# SHDN-IMD-S06-V00-PSU.net
KiCad netlist of a schematic drawn in Altium Designer
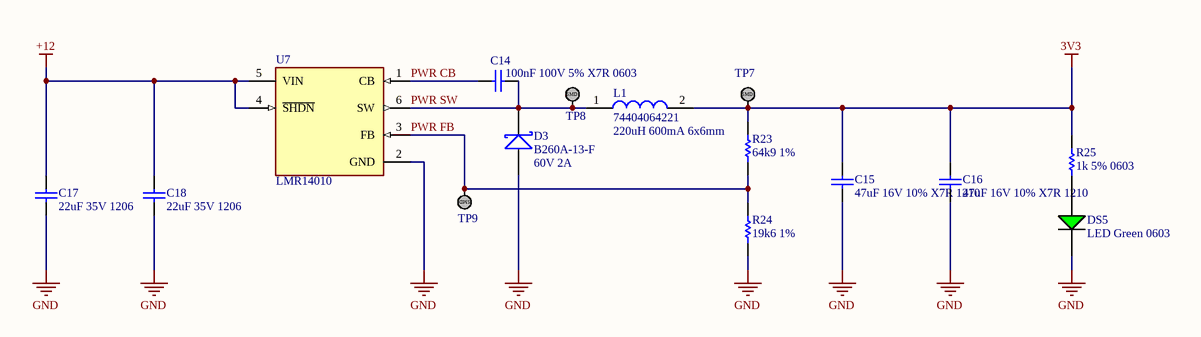
[diagram p0: SHDN-IMD-S06-V00-PSU.SchDoc]

(export (version "E")
  (design (tool "Eeschema 10.0.6"))
  (components
    (comp (ref "C14")
      (value "100nF 100V 5% X7R 0603")
      (footprint "Cap_Ceramic_0603")
      (description "Capacitor, Ceramic, SMD, 100nF, 100V, 5%, X7R, 0603")
      (libsource (lib "StandardCapacitors") (part "100nF 100V 5% X7R 0603"))
    )
    (comp (ref "C15")
      (value "47uF 16V 10% X7R 1210")
      (footprint "Cap_Ceramic_1210")
      (description "Capacitor, Ceramic, SMD, 47uF, 16V, 5%, X7R, 1210")
      (libsource (lib "StandardCapacitors") (part "47uF 16V 10% X7R 1210"))
    )
    (comp (ref "C16")
      (value "47uF 16V 10% X7R 1210")
      (footprint "Cap_Ceramic_1210")
      (description "Capacitor, Ceramic, SMD, 47uF, 16V, 5%, X7R, 1210")
      (libsource (lib "StandardCapacitors") (part "47uF 16V 10% X7R 1210"))
    )
    (comp (ref "C17")
      (value "22uF 35V 1206")
      (footprint "Cap_Ceramic_1206")
      (description "Capacitor, Ceramic, SMD, 22uF, 35V, 10%, X7R, 1206")
      (libsource (lib "StandardCapacitors") (part "22uF 35V 10% X7R 1206"))
    )
    (comp (ref "C18")
      (value "22uF 35V 1206")
      (footprint "Cap_Ceramic_1206")
      (description "Capacitor, Ceramic, SMD, 22uF, 35V, 10%, X7R, 1206")
      (libsource (lib "StandardCapacitors") (part "22uF 35V 10% X7R 1206"))
    )
    (comp (ref "D3")
      (value "B260A-13-F")
      (footprint "SMA")
      (description "Diode, Schottky Barrier Rectifier, 60 V, 2 A, B260A-13-F")
      (libsource (lib "QUTMS_DiodeLibrary") (part "B260A-13-F"))
    )
    (comp (ref "DS5")
      (value "LED Green 0603")
      (footprint "LED GREEN 0603")
      (libsource (lib "QUTMS_LEDLibrary") (part "LED Green 0603"))
    )
    (comp (ref "L1")
      (value "74404064221")
      (footprint "Inductor_6x6mm")
      (description "FIXED IND 220UH 660MA 850 MOHM")
      (libsource (lib "QUTMS_InductorLibrary") (part "74404064221"))
    )
    (comp (ref "R23")
      (value "64k9 1%")
      (footprint "Res_ThinFilm_0603")
      (description "Resistor, SMD, 64k9, 0.1W, 5%, 0603")
      (libsource (lib "StandardResistors") (part "64k9 1% 0603"))
    )
    (comp (ref "R24")
      (value "19k6 1%")
      (footprint "Res_ThinFilm_0603")
      (description "Resistor, SMD, 19k6, 0.1W, 5%, 0603")
      (libsource (lib "StandardResistors") (part "19k6 1% 0603"))
    )
    (comp (ref "R25")
      (value "1k 5% 0603")
      (footprint "Res_ThinFilm_0603")
      (description "Resistor, SMD, 1k, 0.1W, 5%, 0603")
      (libsource (lib "StandardResistors") (part "1k 5% 0603"))
    )
    (comp (ref "TP7")
      (value "TestPoint_SMD")
      (footprint "TestPointSMD")
      (libsource (lib "StandardTest") (part "TestPoint_SMD"))
    )
    (comp (ref "TP8")
      (value "TestPoint_SMD")
      (footprint "TestPointSMD")
      (libsource (lib "StandardTest") (part "TestPoint_SMD"))
    )
    (comp (ref "TP9")
      (value "TestPoint_SMD")
      (footprint "TestPointSMD")
      (libsource (lib "StandardTest") (part "TestPoint_SMD"))
    )
    (comp (ref "U7")
      (value "LMR14010")
      (footprint "LMR14010")
      (libsource (lib "QUTMS_PowerSupplyLibrary") (part "LMR14010"))
    )
  )
  (nets
    (net (code "1") (name "+12") (class "Default")
      (node (ref "C17") (pin "2") (pinfunction "2_2") (pintype "passive"))
      (node (ref "C18") (pin "2") (pinfunction "2_2") (pintype "passive"))
      (node (ref "U7") (pin "4") (pinfunction "~{SHDN}_4") (pintype "input"))
      (node (ref "U7") (pin "5") (pinfunction "VIN_5") (pintype "power_in"))
    )
    (net (code "2") (name "/PWR CB") (class "Default")
      (node (ref "C14") (pin "1") (pinfunction "1_1") (pintype "passive"))
      (node (ref "U7") (pin "1") (pinfunction "CB_1") (pintype "input"))
    )
    (net (code "3") (name "/PWR FB") (class "Default")
      (node (ref "R23") (pin "1") (pinfunction "1_1") (pintype "passive"))
      (node (ref "R24") (pin "2") (pinfunction "2_2") (pintype "passive"))
      (node (ref "TP9") (pin "1") (pinfunction "1_1") (pintype "passive"))
      (node (ref "U7") (pin "3") (pinfunction "FB_3") (pintype "input"))
    )
    (net (code "4") (name "/PWR SW") (class "Default")
      (node (ref "C14") (pin "2") (pinfunction "2_2") (pintype "passive"))
      (node (ref "D3") (pin "K") (pinfunction "K_K") (pintype "passive"))
      (node (ref "L1") (pin "1") (pinfunction "1_1") (pintype "passive"))
      (node (ref "TP8") (pin "1") (pinfunction "1_1") (pintype "passive"))
      (node (ref "U7") (pin "6") (pinfunction "SW_6") (pintype "output"))
    )
    (net (code "5") (name "3V3") (class "Default")
      (node (ref "C15") (pin "2") (pinfunction "2_2") (pintype "passive"))
      (node (ref "C16") (pin "2") (pinfunction "2_2") (pintype "passive"))
      (node (ref "L1") (pin "2") (pinfunction "2_2") (pintype "passive"))
      (node (ref "R23") (pin "2") (pinfunction "2_2") (pintype "passive"))
      (node (ref "R25") (pin "2") (pinfunction "2_2") (pintype "passive"))
      (node (ref "TP7") (pin "1") (pinfunction "1_1") (pintype "passive"))
    )
    (net (code "6") (name "GND") (class "Default")
      (node (ref "C15") (pin "1") (pinfunction "1_1") (pintype "passive"))
      (node (ref "C16") (pin "1") (pinfunction "1_1") (pintype "passive"))
      (node (ref "C17") (pin "1") (pinfunction "1_1") (pintype "passive"))
      (node (ref "C18") (pin "1") (pinfunction "1_1") (pintype "passive"))
      (node (ref "D3") (pin "A") (pinfunction "A_A") (pintype "passive"))
      (node (ref "DS5") (pin "2") (pinfunction "C_2") (pintype "passive"))
      (node (ref "R24") (pin "1") (pinfunction "1_1") (pintype "passive"))
      (node (ref "U7") (pin "2") (pinfunction "GND_2") (pintype "power_in"))
    )
    (net (code "7") (name "Net-(DS5-A)") (class "Default")
      (node (ref "DS5") (pin "1") (pinfunction "A_1") (pintype "passive"))
      (node (ref "R25") (pin "1") (pinfunction "1_1") (pintype "passive"))
    )
  )
)
